# circuit1.net
KiCad netlist of a schematic drawn in EAGLE
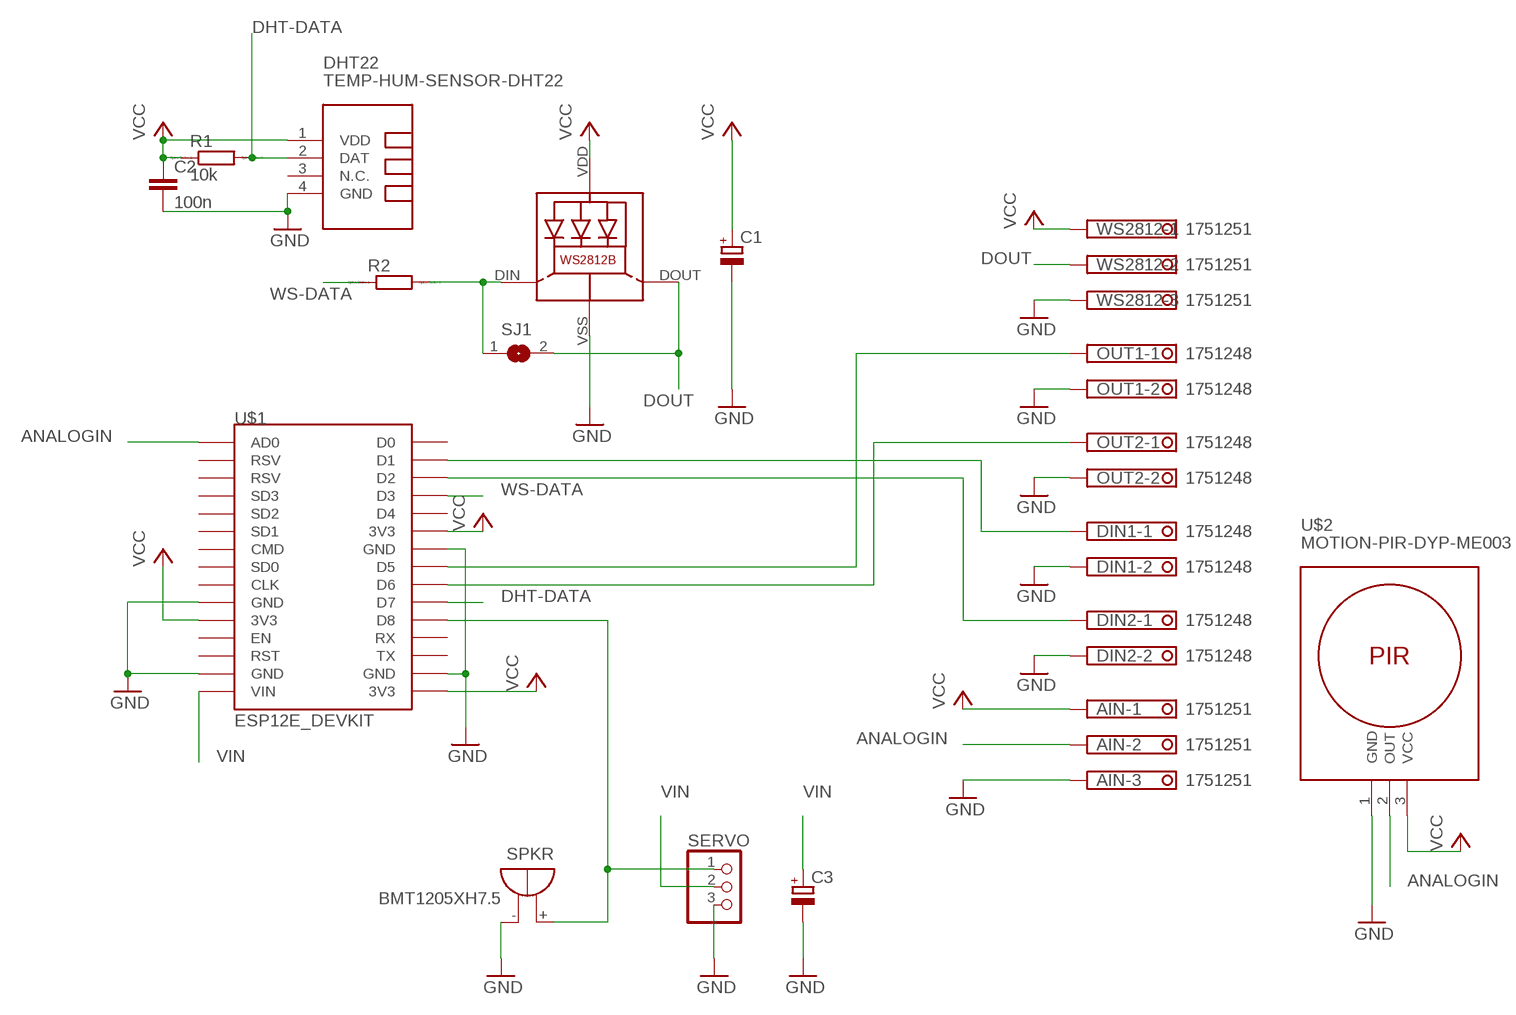
[diagram p0: schematic, sheet 1]

(export (version "E")
  (design (tool "Eeschema 10.0.6"))
  (components
    (comp (ref "AIN")
      (value "1751251")
      (footprint "eagle-import:1751251")
      (libsource (lib "eagle-import") (part "1751251"))
    )
    (comp (ref "C1")
      (value "CPOL-EUE2.5-7")
      (footprint "eagle-import:E2,5-7")
      (libsource (lib "eagle-import") (part "CPOL-EUE2.5-7"))
    )
    (comp (ref "C2")
      (value "100n")
      (footprint "eagle-import:C0805")
      (libsource (lib "eagle-import") (part "C-EUC0805"))
    )
    (comp (ref "C3")
      (value "CPOL-EUE2.5-7")
      (footprint "eagle-import:E2,5-7")
      (libsource (lib "eagle-import") (part "CPOL-EUE2.5-7"))
    )
    (comp (ref "DHT22")
      (value "TEMP-HUM-SENSOR-DHT22")
      (footprint "eagle-import:TEMP-HUM-SENSOR-DHT22")
      (libsource (lib "eagle-import") (part "TEMP-HUM-SENSOR-DHT22"))
    )
    (comp (ref "DIN1")
      (value "1751248")
      (footprint "eagle-import:1751248")
      (libsource (lib "eagle-import") (part "1751248"))
    )
    (comp (ref "DIN2")
      (value "1751248")
      (footprint "eagle-import:1751248")
      (libsource (lib "eagle-import") (part "1751248"))
    )
    (comp (ref "LED1")
      (value "WS2812B")
      (footprint "eagle-import:WS2812B")
      (libsource (lib "eagle-import") (part "WS2812B"))
    )
    (comp (ref "OUT1")
      (value "1751248")
      (footprint "eagle-import:1751248")
      (libsource (lib "eagle-import") (part "1751248"))
    )
    (comp (ref "OUT2")
      (value "1751248")
      (footprint "eagle-import:1751248")
      (libsource (lib "eagle-import") (part "1751248"))
    )
    (comp (ref "R1")
      (value "10k")
      (footprint "eagle-import:0207_10")
      (libsource (lib "eagle-import") (part "R0207/10"))
    )
    (comp (ref "R2")
      (value "R0207/10")
      (footprint "eagle-import:0207_10")
      (libsource (lib "eagle-import") (part "R0207/10"))
    )
    (comp (ref "SERVO")
      (value "PINHD-1X3")
      (footprint "eagle-import:1X03")
      (libsource (lib "eagle-import") (part "PINHD-1X3"))
    )
    (comp (ref "SJ1") (value "SJ") (footprint "eagle-import:SJ") (libsource (lib "eagle-import") (part "SJ")))
    (comp (ref "SPKR")
      (value "BMT1205XH7.5")
      (footprint "eagle-import:BMT1205XH7.5")
      (libsource (lib "eagle-import") (part "BMT1205XH7.5"))
    )
    (comp (ref "U$1")
      (value "ESP12E_DEVKIT")
      (footprint "eagle-import:ESP12E_DEVKIT")
      (libsource (lib "eagle-import") (part "ESP12E_DEVKIT"))
    )
    (comp (ref "U$2")
      (value "MOTION-PIR-DYP-ME003")
      (footprint "eagle-import:MOTION-PIR-DYP-ME003")
      (libsource (lib "eagle-import") (part "MOTION-PIR-DYP-ME003"))
    )
    (comp (ref "WS2812")
      (value "1751251")
      (footprint "eagle-import:1751251")
      (libsource (lib "eagle-import") (part "1751251"))
    )
  )
  (nets
    (net (code "1") (name "/ANALOGIN") (class "Default")
      (node (ref "AIN") (pin "2") (pinfunction "K_2") (pintype "passive"))
      (node (ref "U$1") (pin "AD0") (pinfunction "AD0_AD0") (pintype "bidirectional"))
      (node (ref "U$2") (pin "2") (pinfunction "OUT_2") (pintype "output"))
    )
    (net (code "2") (name "/DHT-DATA") (class "Default")
      (node (ref "DHT22") (pin "2") (pinfunction "DAT_2") (pintype "bidirectional"))
      (node (ref "R1") (pin "2") (pinfunction "2_2") (pintype "passive"))
      (node (ref "U$1") (pin "D7") (pinfunction "D7_D7") (pintype "bidirectional"))
    )
    (net (code "3") (name "/DOUT") (class "Default")
      (node (ref "LED1") (pin "DOUT") (pinfunction "DO_DOUT") (pintype "output"))
      (node (ref "SJ1") (pin "2") (pinfunction "2_2") (pintype "passive"))
      (node (ref "WS2812") (pin "2") (pinfunction "K_2") (pintype "passive"))
    )
    (net (code "4") (name "/VIN") (class "Default")
      (node (ref "C3") (pin "+") (pinfunction "+_+") (pintype "passive"))
      (node (ref "SERVO") (pin "2") (pinfunction "2_2") (pintype "passive"))
      (node (ref "U$1") (pin "VIN") (pinfunction "VIN_VIN") (pintype "bidirectional"))
    )
    (net (code "5") (name "/WS-DATA") (class "Default")
      (node (ref "R2") (pin "1") (pinfunction "1_1") (pintype "passive"))
      (node (ref "U$1") (pin "D3") (pinfunction "D3_D3") (pintype "bidirectional"))
    )
    (net (code "6") (name "GND") (class "Default")
      (node (ref "AIN") (pin "3") (pinfunction "K_3") (pintype "passive"))
      (node (ref "C1") (pin "-") (pinfunction "-_-") (pintype "passive"))
      (node (ref "C2") (pin "2") (pinfunction "2_2") (pintype "passive"))
      (node (ref "C3") (pin "-") (pinfunction "-_-") (pintype "passive"))
      (node (ref "DHT22") (pin "4") (pinfunction "GND_4") (pintype "power_in"))
      (node (ref "DIN1") (pin "2") (pinfunction "K_2") (pintype "passive"))
      (node (ref "DIN2") (pin "2") (pinfunction "K_2") (pintype "passive"))
      (node (ref "LED1") (pin "VSS") (pinfunction "GND_VSS") (pintype "power_in"))
      (node (ref "OUT1") (pin "2") (pinfunction "K_2") (pintype "passive"))
      (node (ref "OUT2") (pin "2") (pinfunction "K_2") (pintype "passive"))
      (node (ref "SERVO") (pin "3") (pinfunction "3_3") (pintype "passive"))
      (node (ref "SPKR") (pin "-") (pinfunction "-_-") (pintype "passive"))
      (node (ref "U$1") (pin "GND@0") (pinfunction "GND_GND@0") (pintype "bidirectional"))
      (node (ref "U$1") (pin "GND@1") (pinfunction "GND_GND@1") (pintype "bidirectional"))
      (node (ref "U$1") (pin "GND@2") (pinfunction "GND_GND@2") (pintype "bidirectional"))
      (node (ref "U$1") (pin "GND@3") (pinfunction "GND_GND@3") (pintype "bidirectional"))
      (node (ref "U$2") (pin "1") (pinfunction "GND_1") (pintype "power_in"))
      (node (ref "WS2812") (pin "3") (pinfunction "K_3") (pintype "passive"))
    )
    (net (code "7") (name "Net-(DIN1A-K)") (class "Default")
      (node (ref "DIN1") (pin "1") (pinfunction "K_1") (pintype "passive"))
      (node (ref "U$1") (pin "D1") (pinfunction "D1_D1") (pintype "bidirectional"))
    )
    (net (code "8") (name "Net-(DIN2A-K)") (class "Default")
      (node (ref "DIN2") (pin "1") (pinfunction "K_1") (pintype "passive"))
      (node (ref "U$1") (pin "D2") (pinfunction "D2_D2") (pintype "bidirectional"))
    )
    (net (code "9") (name "Net-(LED1-DI)") (class "Default")
      (node (ref "LED1") (pin "DIN") (pinfunction "DI_DIN") (pintype "input"))
      (node (ref "R2") (pin "2") (pinfunction "2_2") (pintype "passive"))
      (node (ref "SJ1") (pin "1") (pinfunction "1_1") (pintype "passive"))
    )
    (net (code "10") (name "Net-(OUT1A-K)") (class "Default")
      (node (ref "OUT1") (pin "1") (pinfunction "K_1") (pintype "passive"))
      (node (ref "U$1") (pin "D5") (pinfunction "D5_D5") (pintype "bidirectional"))
    )
    (net (code "11") (name "Net-(OUT2A-K)") (class "Default")
      (node (ref "OUT2") (pin "1") (pinfunction "K_1") (pintype "passive"))
      (node (ref "U$1") (pin "D6") (pinfunction "D6_D6") (pintype "bidirectional"))
    )
    (net (code "12") (name "Net-(SERVO-Pad1)") (class "Default")
      (node (ref "SERVO") (pin "1") (pinfunction "1_1") (pintype "passive"))
      (node (ref "SPKR") (pin "+") (pinfunction "+_+") (pintype "passive"))
      (node (ref "U$1") (pin "D8") (pinfunction "D8_D8") (pintype "bidirectional"))
    )
    (net (code "13") (name "VCC") (class "Default")
      (node (ref "AIN") (pin "1") (pinfunction "K_1") (pintype "passive"))
      (node (ref "C1") (pin "+") (pinfunction "+_+") (pintype "passive"))
      (node (ref "C2") (pin "1") (pinfunction "1_1") (pintype "passive"))
      (node (ref "DHT22") (pin "1") (pinfunction "VDD_1") (pintype "power_in"))
      (node (ref "LED1") (pin "VDD") (pinfunction "VDD_VDD") (pintype "power_in"))
      (node (ref "R1") (pin "1") (pinfunction "1_1") (pintype "passive"))
      (node (ref "U$1") (pin "3V3@0") (pinfunction "3V3_3V3@0") (pintype "bidirectional"))
      (node (ref "U$1") (pin "3V3@1") (pinfunction "3V3_3V3@1") (pintype "bidirectional"))
      (node (ref "U$1") (pin "3V3@2") (pinfunction "3V3_3V3@2") (pintype "bidirectional"))
      (node (ref "U$2") (pin "3") (pinfunction "VCC_3") (pintype "power_in"))
      (node (ref "WS2812") (pin "1") (pinfunction "K_1") (pintype "passive"))
    )
    (net (code "14") (name "unconnected-(DHT22-N.C.-Pad3)") (class "Default")
      (node (ref "DHT22") (pin "3") (pinfunction "N.C._3") (pintype "passive"))
    )
    (net (code "15") (name "unconnected-(U$1-PadCLK)") (class "Default")
      (node (ref "U$1") (pin "CLK") (pinfunction "CLK_CLK") (pintype "bidirectional"))
    )
    (net (code "16") (name "unconnected-(U$1-PadCMD)") (class "Default")
      (node (ref "U$1") (pin "CMD") (pinfunction "CMD_CMD") (pintype "bidirectional"))
    )
    (net (code "17") (name "unconnected-(U$1-PadD0)") (class "Default")
      (node (ref "U$1") (pin "D0") (pinfunction "D0_D0") (pintype "bidirectional"))
    )
    (net (code "18") (name "unconnected-(U$1-PadD4)") (class "Default")
      (node (ref "U$1") (pin "D4") (pinfunction "D4_D4") (pintype "bidirectional"))
    )
    (net (code "19") (name "unconnected-(U$1-PadEN)") (class "Default")
      (node (ref "U$1") (pin "EN") (pinfunction "EN_EN") (pintype "bidirectional"))
    )
    (net (code "20") (name "unconnected-(U$1-PadRST)") (class "Default")
      (node (ref "U$1") (pin "RST") (pinfunction "RST_RST") (pintype "bidirectional"))
    )
    (net (code "21") (name "unconnected-(U$1-PadRX)") (class "Default")
      (node (ref "U$1") (pin "RX") (pinfunction "RX_RX") (pintype "bidirectional"))
    )
    (net (code "22") (name "unconnected-(U$1-PadSD0)") (class "Default")
      (node (ref "U$1") (pin "SD0") (pinfunction "SD0_SD0") (pintype "bidirectional"))
    )
    (net (code "23") (name "unconnected-(U$1-PadSD1)") (class "Default")
      (node (ref "U$1") (pin "SD1") (pinfunction "SD1_SD1") (pintype "bidirectional"))
    )
    (net (code "24") (name "unconnected-(U$1-PadSD2)") (class "Default")
      (node (ref "U$1") (pin "SD2") (pinfunction "SD2_SD2") (pintype "bidirectional"))
    )
    (net (code "25") (name "unconnected-(U$1-PadSD3)") (class "Default")
      (node (ref "U$1") (pin "SD3") (pinfunction "SD3_SD3") (pintype "bidirectional"))
    )
    (net (code "26") (name "unconnected-(U$1-PadTX)") (class "Default")
      (node (ref "U$1") (pin "TX") (pinfunction "TX_TX") (pintype "bidirectional"))
    )
    (net (code "27") (name "unconnected-(U$1-RSV-PadRSV@0)") (class "Default")
      (node (ref "U$1") (pin "RSV@0") (pinfunction "RSV_RSV@0") (pintype "bidirectional"))
    )
    (net (code "28") (name "unconnected-(U$1-RSV-PadRSV@1)") (class "Default")
      (node (ref "U$1") (pin "RSV@1") (pinfunction "RSV_RSV@1") (pintype "bidirectional"))
    )
  )
)
